# hole_field_direct.net
KiCad netlist of a schematic drawn in Altium Designer
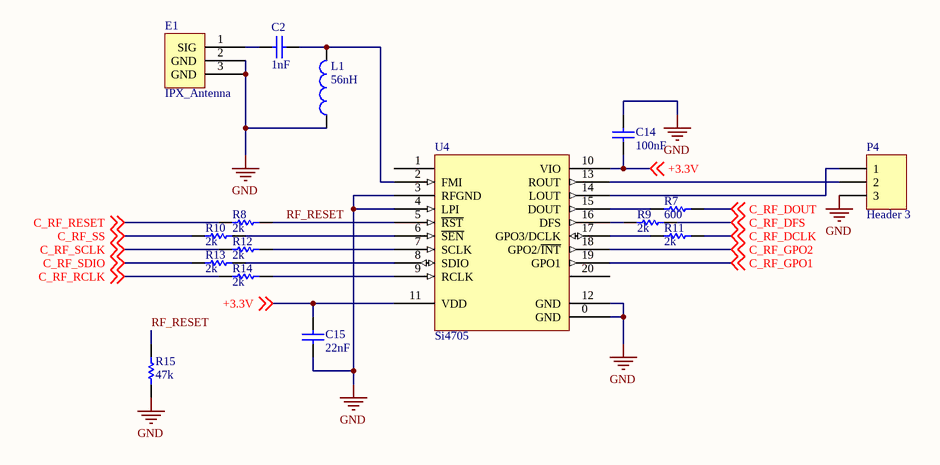
[diagram p0: hole_field_direct.SchDoc]

(export (version "E")
  (design (tool "Eeschema 10.0.6"))
  (components
    (comp (ref "C2")
      (value "1nF")
      (footprint "CHIP0402")
      (description "Capacitor")
      (fields (field (name "PUBLISHER") "Altium Limited"))
      (libsource (lib "Miscellaneous Devices") (part "Cap"))
    )
    (comp (ref "C14")
      (value "100nF")
      (footprint "CHIP0402")
      (description "Capacitor")
      (fields (field (name "PUBLISHER") "Altium Limited"))
      (libsource (lib "Miscellaneous Devices") (part "Cap"))
    )
    (comp (ref "C15")
      (value "22nF")
      (footprint "CHIP0402")
      (description "Capacitor")
      (fields (field (name "PUBLISHER") "Altium Limited"))
      (libsource (lib "Miscellaneous Devices") (part "Cap"))
    )
    (comp (ref "E1") (value "IPX_Antenna") (footprint "IPX-M") (libsource (lib "mil01") (part "IPX_Antenna")))
    (comp (ref "L1")
      (value "56nH")
      (footprint "0402-A")
      (description "Inductor")
      (fields (field (name "PUBLISHER") "Altium Limited"))
      (libsource (lib "Miscellaneous Devices") (part "Inductor"))
    )
    (comp (ref "P4")
      (value "Header 3")
      (footprint "HDR1X3")
      (description "Header, 3-Pin")
      (fields (field (name "PUBLISHER") "Altium Limited"))
      (libsource (lib "Miscellaneous Connectors") (part "Header 3"))
    )
    (comp (ref "R7")
      (value "600")
      (footprint "CHIP0402")
      (description "Resistor")
      (fields (field (name "PUBLISHER") "Altium Limited"))
      (libsource (lib "Miscellaneous Devices") (part "Res1"))
    )
    (comp (ref "R8")
      (value "2k")
      (footprint "CHIP0402")
      (description "Resistor")
      (fields (field (name "PUBLISHER") "Altium Limited"))
      (libsource (lib "Miscellaneous Devices") (part "Res1"))
    )
    (comp (ref "R9")
      (value "2k")
      (footprint "CHIP0402")
      (description "Resistor")
      (fields (field (name "PUBLISHER") "Altium Limited"))
      (libsource (lib "Miscellaneous Devices") (part "Res1"))
    )
    (comp (ref "R10")
      (value "2k")
      (footprint "CHIP0402")
      (description "Resistor")
      (fields (field (name "PUBLISHER") "Altium Limited"))
      (libsource (lib "Miscellaneous Devices") (part "Res1"))
    )
    (comp (ref "R11")
      (value "2k")
      (footprint "CHIP0402")
      (description "Resistor")
      (fields (field (name "PUBLISHER") "Altium Limited"))
      (libsource (lib "Miscellaneous Devices") (part "Res1"))
    )
    (comp (ref "R12")
      (value "2k")
      (footprint "CHIP0402")
      (description "Resistor")
      (fields (field (name "PUBLISHER") "Altium Limited"))
      (libsource (lib "Miscellaneous Devices") (part "Res1"))
    )
    (comp (ref "R13")
      (value "2k")
      (footprint "CHIP0402")
      (description "Resistor")
      (fields (field (name "PUBLISHER") "Altium Limited"))
      (libsource (lib "Miscellaneous Devices") (part "Res1"))
    )
    (comp (ref "R14")
      (value "2k")
      (footprint "CHIP0402")
      (description "Resistor")
      (fields (field (name "PUBLISHER") "Altium Limited"))
      (libsource (lib "Miscellaneous Devices") (part "Res1"))
    )
    (comp (ref "R15")
      (value "47k")
      (footprint "CHIP0402")
      (description "Resistor")
      (fields (field (name "PUBLISHER") "Altium Limited"))
      (libsource (lib "Miscellaneous Devices") (part "Res1"))
    )
    (comp (ref "U4")
      (value "Si4705")
      (footprint "QFN50P300X300X60-20N")
      (libsource (lib "mil01") (part "Si4705"))
    )
  )
  (nets
    (net (code "1") (name "+3.3V") (class "Default")
      (node (ref "C14") (pin "1") (pinfunction "1_1") (pintype "passive"))
      (node (ref "C15") (pin "2") (pinfunction "2_2") (pintype "passive"))
      (node (ref "U4") (pin "10") (pinfunction "VIO_10") (pintype "power_in"))
      (node (ref "U4") (pin "11") (pinfunction "VDD_11") (pintype "power_in"))
    )
    (net (code "2") (name "/RF_RESET") (class "Default")
      (node (ref "R15") (pin "2") (pinfunction "2_2") (pintype "passive"))
      (node (ref "R8") (pin "2") (pinfunction "2_2") (pintype "passive"))
      (node (ref "U4") (pin "5") (pinfunction "~{RST}_5") (pintype "input"))
    )
    (net (code "3") (name "C_RF_DCLK") (class "Default")
      (node (ref "R11") (pin "2") (pinfunction "2_2") (pintype "passive"))
    )
    (net (code "4") (name "C_RF_DFS") (class "Default")
      (node (ref "R9") (pin "2") (pinfunction "2_2") (pintype "passive"))
    )
    (net (code "5") (name "C_RF_DOUT") (class "Default")
      (node (ref "R7") (pin "2") (pinfunction "2_2") (pintype "passive"))
    )
    (net (code "6") (name "C_RF_GPO1") (class "Default")
      (node (ref "U4") (pin "19") (pinfunction "GPO1_19") (pintype "output"))
    )
    (net (code "7") (name "C_RF_GPO2") (class "Default")
      (node (ref "U4") (pin "18") (pinfunction "GPO2/~{INT}_18") (pintype "output"))
    )
    (net (code "8") (name "C_RF_RCLK") (class "Default")
      (node (ref "R14") (pin "1") (pinfunction "1_1") (pintype "passive"))
    )
    (net (code "9") (name "C_RF_RESET") (class "Default")
      (node (ref "R8") (pin "1") (pinfunction "1_1") (pintype "passive"))
    )
    (net (code "10") (name "C_RF_SCLK") (class "Default")
      (node (ref "R12") (pin "1") (pinfunction "1_1") (pintype "passive"))
    )
    (net (code "11") (name "C_RF_SDIO") (class "Default")
      (node (ref "R13") (pin "1") (pinfunction "1_1") (pintype "passive"))
    )
    (net (code "12") (name "C_RF_SS") (class "Default")
      (node (ref "R10") (pin "1") (pinfunction "1_1") (pintype "passive"))
    )
    (net (code "13") (name "GND") (class "Default")
      (node (ref "C14") (pin "2") (pinfunction "2_2") (pintype "passive"))
      (node (ref "C15") (pin "1") (pinfunction "1_1") (pintype "passive"))
      (node (ref "E1") (pin "2") (pinfunction "GND_2") (pintype "passive"))
      (node (ref "E1") (pin "3") (pinfunction "GND_3") (pintype "passive"))
      (node (ref "L1") (pin "1") (pinfunction "1_1") (pintype "passive"))
      (node (ref "P4") (pin "3") (pinfunction "3_3") (pintype "passive"))
      (node (ref "R15") (pin "1") (pinfunction "1_1") (pintype "passive"))
      (node (ref "U4") (pin "0") (pinfunction "GND_0") (pintype "power_in"))
      (node (ref "U4") (pin "12") (pinfunction "GND_12") (pintype "power_in"))
      (node (ref "U4") (pin "3") (pinfunction "RFGND_3") (pintype "power_in"))
      (node (ref "U4") (pin "4") (pinfunction "LPI_4") (pintype "input"))
    )
    (net (code "14") (name "Net-(E1-SIG)") (class "Default")
      (node (ref "C2") (pin "2") (pinfunction "2_2") (pintype "passive"))
      (node (ref "E1") (pin "1") (pinfunction "SIG_1") (pintype "passive"))
    )
    (net (code "15") (name "Net-(U4-DFS)") (class "Default")
      (node (ref "R9") (pin "1") (pinfunction "1_1") (pintype "passive"))
      (node (ref "U4") (pin "16") (pinfunction "DFS_16") (pintype "output"))
    )
    (net (code "16") (name "Net-(U4-DOUT)") (class "Default")
      (node (ref "R7") (pin "1") (pinfunction "1_1") (pintype "passive"))
      (node (ref "U4") (pin "15") (pinfunction "DOUT_15") (pintype "output"))
    )
    (net (code "17") (name "Net-(U4-FMI)") (class "Default")
      (node (ref "C2") (pin "1") (pinfunction "1_1") (pintype "passive"))
      (node (ref "L1") (pin "2") (pinfunction "2_2") (pintype "passive"))
      (node (ref "U4") (pin "2") (pinfunction "FMI_2") (pintype "input"))
    )
    (net (code "18") (name "Net-(U4-GPO3{slash}DCLK)") (class "Default")
      (node (ref "R11") (pin "1") (pinfunction "1_1") (pintype "passive"))
      (node (ref "U4") (pin "17") (pinfunction "GPO3/DCLK_17") (pintype "bidirectional"))
    )
    (net (code "19") (name "Net-(U4-LOUT)") (class "Default")
      (node (ref "P4") (pin "1") (pinfunction "1_1") (pintype "passive"))
      (node (ref "U4") (pin "14") (pinfunction "LOUT_14") (pintype "output"))
    )
    (net (code "20") (name "Net-(U4-RCLK)") (class "Default")
      (node (ref "R14") (pin "2") (pinfunction "2_2") (pintype "passive"))
      (node (ref "U4") (pin "9") (pinfunction "RCLK_9") (pintype "input"))
    )
    (net (code "21") (name "Net-(U4-ROUT)") (class "Default")
      (node (ref "P4") (pin "2") (pinfunction "2_2") (pintype "passive"))
      (node (ref "U4") (pin "13") (pinfunction "ROUT_13") (pintype "output"))
    )
    (net (code "22") (name "Net-(U4-SCLK)") (class "Default")
      (node (ref "R12") (pin "2") (pinfunction "2_2") (pintype "passive"))
      (node (ref "U4") (pin "7") (pinfunction "SCLK_7") (pintype "input"))
    )
    (net (code "23") (name "Net-(U4-SDIO)") (class "Default")
      (node (ref "R13") (pin "2") (pinfunction "2_2") (pintype "passive"))
      (node (ref "U4") (pin "8") (pinfunction "SDIO_8") (pintype "bidirectional"))
    )
    (net (code "24") (name "Net-(U4-~{SEN})") (class "Default")
      (node (ref "R10") (pin "2") (pinfunction "2_2") (pintype "passive"))
      (node (ref "U4") (pin "6") (pinfunction "~{SEN}_6") (pintype "input"))
    )
    (net (code "25") (name "unconnected-(U4-NC-Pad1)") (class "Default")
      (node (ref "U4") (pin "1") (pinfunction "NC_1") (pintype "passive"))
    )
    (net (code "26") (name "unconnected-(U4-NC-Pad20)") (class "Default")
      (node (ref "U4") (pin "20") (pinfunction "NC_20") (pintype "passive"))
    )
  )
)
